# ConverterModule12V18A.net
KiCad netlist of a schematic drawn in Altium Designer
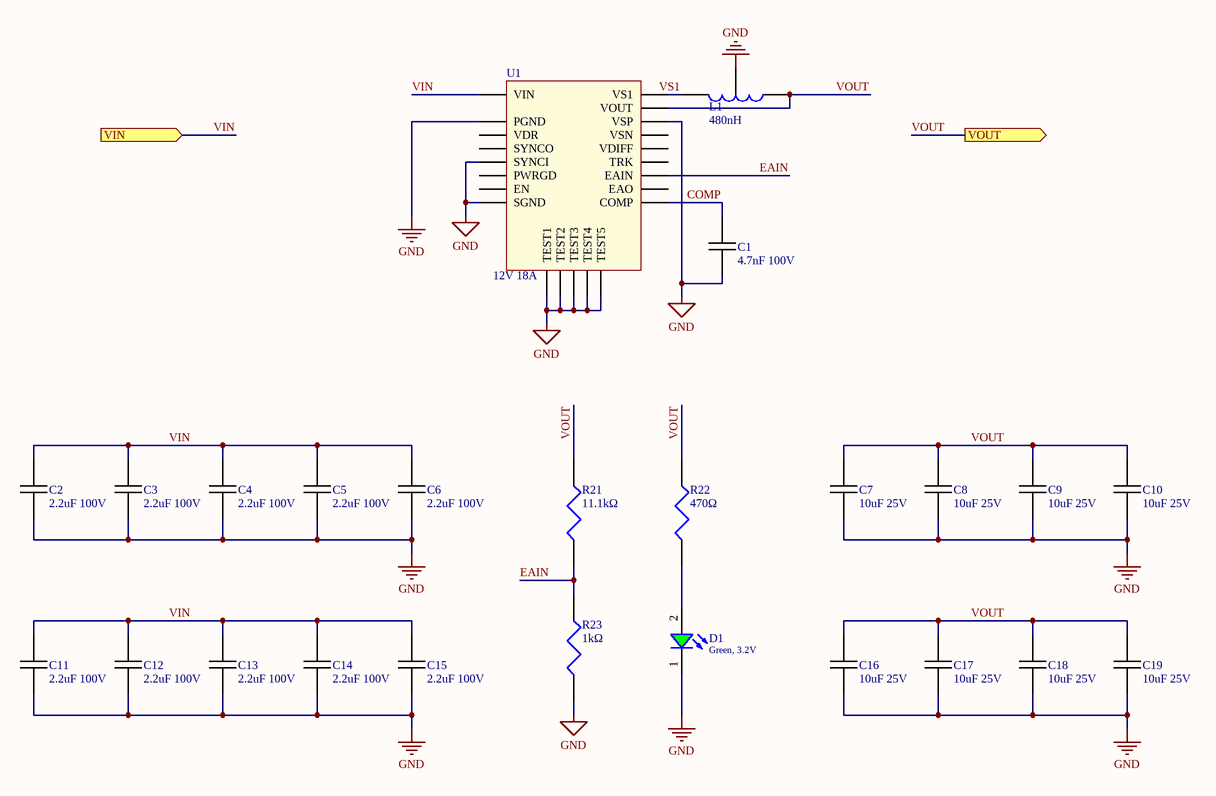
[diagram p0: ConverterModule12V18A.SchDoc]

(export (version "E")
  (design (tool "Eeschema 10.0.6"))
  (components
    (comp (ref "C1")
      (value "4.7nF 100V")
      (footprint "C1608 Generic")
      (description "TDK CAP CER 4700PF 100V C0G 0603")
      (fields
        (field (name "PART NUMBER") "C1608C0G2A472J080AC")
        (field (name "MANUFACTURER") "TDK Corporation")
      )
      (libsource (lib "MinesROV") (part "C1608C0G2A472J080AC"))
    )
    (comp (ref "C2")
      (value "2.2uF 100V")
      (footprint "HMK325B7225MM-P")
      (description "Taiyo Yuden CAP CER 2.2UF 100V X7R 1210")
      (fields (field (name "PART NUMBER") "HMK325B7225MM-P") (field (name "MANUFACTURER") "Taiyo Yuden"))
      (libsource (lib "MinesROV") (part "HMK325B7225MM-P"))
    )
    (comp (ref "C3")
      (value "2.2uF 100V")
      (footprint "HMK325B7225MM-P")
      (description "Taiyo Yuden CAP CER 2.2UF 100V X7R 1210")
      (fields (field (name "PART NUMBER") "HMK325B7225MM-P") (field (name "MANUFACTURER") "Taiyo Yuden"))
      (libsource (lib "MinesROV") (part "HMK325B7225MM-P"))
    )
    (comp (ref "C4")
      (value "2.2uF 100V")
      (footprint "HMK325B7225MM-P")
      (description "Taiyo Yuden CAP CER 2.2UF 100V X7R 1210")
      (fields (field (name "PART NUMBER") "HMK325B7225MM-P") (field (name "MANUFACTURER") "Taiyo Yuden"))
      (libsource (lib "MinesROV") (part "HMK325B7225MM-P"))
    )
    (comp (ref "C5")
      (value "2.2uF 100V")
      (footprint "HMK325B7225MM-P")
      (description "Taiyo Yuden CAP CER 2.2UF 100V X7R 1210")
      (fields (field (name "PART NUMBER") "HMK325B7225MM-P") (field (name "MANUFACTURER") "Taiyo Yuden"))
      (libsource (lib "MinesROV") (part "HMK325B7225MM-P"))
    )
    (comp (ref "C6")
      (value "2.2uF 100V")
      (footprint "HMK325B7225MM-P")
      (description "Taiyo Yuden CAP CER 2.2UF 100V X7R 1210")
      (fields (field (name "PART NUMBER") "HMK325B7225MM-P") (field (name "MANUFACTURER") "Taiyo Yuden"))
      (libsource (lib "MinesROV") (part "HMK325B7225MM-P"))
    )
    (comp (ref "C7")
      (value "10uF 25V")
      (footprint "C1210C106M3RACTU")
      (description "KEMET CAP CER 10UF 25V X7R 1210")
      (fields (field (name "PART NUMBER") "C1210C106M3RACTU") (field (name "MANUFACTURER") "KEMET"))
      (libsource (lib "MinesROV") (part "C1210C106M3RACTU"))
    )
    (comp (ref "C8")
      (value "10uF 25V")
      (footprint "C1210C106M3RACTU")
      (description "KEMET CAP CER 10UF 25V X7R 1210")
      (fields (field (name "PART NUMBER") "C1210C106M3RACTU") (field (name "MANUFACTURER") "KEMET"))
      (libsource (lib "MinesROV") (part "C1210C106M3RACTU"))
    )
    (comp (ref "C9")
      (value "10uF 25V")
      (footprint "C1210C106M3RACTU")
      (description "KEMET CAP CER 10UF 25V X7R 1210")
      (fields (field (name "PART NUMBER") "C1210C106M3RACTU") (field (name "MANUFACTURER") "KEMET"))
      (libsource (lib "MinesROV") (part "C1210C106M3RACTU"))
    )
    (comp (ref "C10")
      (value "10uF 25V")
      (footprint "C1210C106M3RACTU")
      (description "KEMET CAP CER 10UF 25V X7R 1210")
      (fields (field (name "PART NUMBER") "C1210C106M3RACTU") (field (name "MANUFACTURER") "KEMET"))
      (libsource (lib "MinesROV") (part "C1210C106M3RACTU"))
    )
    (comp (ref "C11")
      (value "2.2uF 100V")
      (footprint "HMK325B7225MM-P")
      (description "Taiyo Yuden CAP CER 2.2UF 100V X7R 1210")
      (fields (field (name "PART NUMBER") "HMK325B7225MM-P") (field (name "MANUFACTURER") "Taiyo Yuden"))
      (libsource (lib "MinesROV") (part "HMK325B7225MM-P"))
    )
    (comp (ref "C12")
      (value "2.2uF 100V")
      (footprint "HMK325B7225MM-P")
      (description "Taiyo Yuden CAP CER 2.2UF 100V X7R 1210")
      (fields (field (name "PART NUMBER") "HMK325B7225MM-P") (field (name "MANUFACTURER") "Taiyo Yuden"))
      (libsource (lib "MinesROV") (part "HMK325B7225MM-P"))
    )
    (comp (ref "C13")
      (value "2.2uF 100V")
      (footprint "HMK325B7225MM-P")
      (description "Taiyo Yuden CAP CER 2.2UF 100V X7R 1210")
      (fields (field (name "PART NUMBER") "HMK325B7225MM-P") (field (name "MANUFACTURER") "Taiyo Yuden"))
      (libsource (lib "MinesROV") (part "HMK325B7225MM-P"))
    )
    (comp (ref "C14")
      (value "2.2uF 100V")
      (footprint "HMK325B7225MM-P")
      (description "Taiyo Yuden CAP CER 2.2UF 100V X7R 1210")
      (fields (field (name "PART NUMBER") "HMK325B7225MM-P") (field (name "MANUFACTURER") "Taiyo Yuden"))
      (libsource (lib "MinesROV") (part "HMK325B7225MM-P"))
    )
    (comp (ref "C15")
      (value "2.2uF 100V")
      (footprint "HMK325B7225MM-P")
      (description "Taiyo Yuden CAP CER 2.2UF 100V X7R 1210")
      (fields (field (name "PART NUMBER") "HMK325B7225MM-P") (field (name "MANUFACTURER") "Taiyo Yuden"))
      (libsource (lib "MinesROV") (part "HMK325B7225MM-P"))
    )
    (comp (ref "C16")
      (value "10uF 25V")
      (footprint "C1210C106M3RACTU")
      (description "KEMET CAP CER 10UF 25V X7R 1210")
      (fields (field (name "PART NUMBER") "C1210C106M3RACTU") (field (name "MANUFACTURER") "KEMET"))
      (libsource (lib "MinesROV") (part "C1210C106M3RACTU"))
    )
    (comp (ref "C17")
      (value "10uF 25V")
      (footprint "C1210C106M3RACTU")
      (description "KEMET CAP CER 10UF 25V X7R 1210")
      (fields (field (name "PART NUMBER") "C1210C106M3RACTU") (field (name "MANUFACTURER") "KEMET"))
      (libsource (lib "MinesROV") (part "C1210C106M3RACTU"))
    )
    (comp (ref "C18")
      (value "10uF 25V")
      (footprint "C1210C106M3RACTU")
      (description "KEMET CAP CER 10UF 25V X7R 1210")
      (fields (field (name "PART NUMBER") "C1210C106M3RACTU") (field (name "MANUFACTURER") "KEMET"))
      (libsource (lib "MinesROV") (part "C1210C106M3RACTU"))
    )
    (comp (ref "C19")
      (value "10uF 25V")
      (footprint "C1210C106M3RACTU")
      (description "KEMET CAP CER 10UF 25V X7R 1210")
      (fields (field (name "PART NUMBER") "C1210C106M3RACTU") (field (name "MANUFACTURER") "KEMET"))
      (libsource (lib "MinesROV") (part "C1210C106M3RACTU"))
    )
    (comp (ref "D1")
      (value "Green, 3.2V")
      (footprint "WL-SMCW_1206")
      (description "WL-SMCW SMT Mono-color Chip LED Waterclear, size 1206, Green, 3.2V, 140deg")
      (fields (field (name "PART NUMBER") "150120GS75000") (field (name "PUBLISHER") "Wurth Elektronik"))
      (libsource (lib "MinesROV") (part "150120GS75000"))
    )
    (comp (ref "L1")
      (value "480nH")
      (footprint "PA5120.481NLT")
      (description "Pulse FIXED IND 480NH 32A 1.7MOHM SMD")
      (fields
        (field (name "MANUFACTURER") "Pulse Electronics Power")
        (field (name "PART NUMBER") "PA5120.481NLT")
      )
      (libsource (lib "MinesROV") (part "PA5120.481NLT"))
    )
    (comp (ref "R21")
      (value "11.1kΩ")
      (footprint "RNCF0603 Generic")
      (description "Stackpole RES 11.1K OHM 0.1% 1/10W 0603")
      (fields
        (field (name "PART NUMBER") "RNCF0603BTE11K1")
        (field (name "MANUFACTURER") "Stackpole Electronics Inc")
      )
      (libsource (lib "MinesROV") (part "RNCF0603BTE11K1"))
    )
    (comp (ref "R22")
      (value "470Ω")
      (footprint "RMCF1206")
      (description "Stackpole RES 470 OHM 5% 1/4W 1206")
      (fields
        (field (name "PART NUMBER") "RMCF1206JT470R")
        (field (name "MANUFACTURER") "Stackpole Electronics Inc")
      )
      (libsource (lib "MinesROV") (part "RMCF1206JT470R"))
    )
    (comp (ref "R23")
      (value "1kΩ")
      (footprint "RNCF0603 Generic")
      (description "Stackpole RES 1K OHM 0.01% 1/10W 0603")
      (fields
        (field (name "PART NUMBER") "RNCF0603TKY1K00")
        (field (name "MANUFACTURER") "Stackpole Electronics Inc")
      )
      (libsource (lib "MinesROV") (part "RNCF0603TKY1K00"))
    )
    (comp (ref "U1")
      (value "12V 18A")
      (footprint "PI3526-00-LGIZ")
      (description "Vicor DC DC CONVERTER 12V 18A")
      (fields (field (name "MANUFACTURER") "Vicor Corporation") (field (name "PART NUMBER") "PI3526-00-LGIZ"))
      (libsource (lib "MinesROV") (part "PI3526-00-LGIZ"))
    )
  )
  (nets
    (net (code "1") (name "/COMP") (class "Default")
      (node (ref "C1") (pin "1") (pinfunction "1_1") (pintype "passive"))
      (node (ref "U1") (pin "B1") (pinfunction "COMP_B1") (pintype "passive"))
    )
    (net (code "2") (name "/EAIN") (class "Default")
      (node (ref "R21") (pin "2") (pinfunction "2_2") (pintype "passive"))
      (node (ref "R23") (pin "2") (pinfunction "2_2") (pintype "passive"))
      (node (ref "U1") (pin "A2") (pinfunction "EAIN_A2") (pintype "passive"))
    )
    (net (code "3") (name "/VIN") (class "Default")
      (node (ref "C11") (pin "1") (pinfunction "1_1") (pintype "passive"))
      (node (ref "C12") (pin "1") (pinfunction "1_1") (pintype "passive"))
      (node (ref "C13") (pin "1") (pinfunction "1_1") (pintype "passive"))
      (node (ref "C14") (pin "1") (pinfunction "1_1") (pintype "passive"))
      (node (ref "C15") (pin "1") (pinfunction "1_1") (pintype "passive"))
      (node (ref "C2") (pin "1") (pinfunction "1_1") (pintype "passive"))
      (node (ref "C3") (pin "1") (pinfunction "1_1") (pintype "passive"))
      (node (ref "C4") (pin "1") (pinfunction "1_1") (pintype "passive"))
      (node (ref "C5") (pin "1") (pinfunction "1_1") (pintype "passive"))
      (node (ref "C6") (pin "1") (pinfunction "1_1") (pintype "passive"))
      (node (ref "U1") (pin "BLOCK3") (pinfunction "VIN_BLOCK3") (pintype "passive"))
    )
    (net (code "4") (name "/VOUT") (class "Default")
      (node (ref "C10") (pin "2") (pinfunction "2_2") (pintype "passive"))
      (node (ref "C16") (pin "2") (pinfunction "2_2") (pintype "passive"))
      (node (ref "C17") (pin "2") (pinfunction "2_2") (pintype "passive"))
      (node (ref "C18") (pin "2") (pinfunction "2_2") (pintype "passive"))
      (node (ref "C19") (pin "2") (pinfunction "2_2") (pintype "passive"))
      (node (ref "C7") (pin "2") (pinfunction "2_2") (pintype "passive"))
      (node (ref "C8") (pin "2") (pinfunction "2_2") (pintype "passive"))
      (node (ref "C9") (pin "2") (pinfunction "2_2") (pintype "passive"))
      (node (ref "L1") (pin "1") (pinfunction "1_1") (pintype "passive"))
      (node (ref "R21") (pin "1") (pinfunction "1_1") (pintype "passive"))
      (node (ref "R22") (pin "2") (pinfunction "2_2") (pintype "passive"))
      (node (ref "U1") (pin "BLOCK4") (pinfunction "VOUT_BLOCK4") (pintype "passive"))
    )
    (net (code "5") (name "/VS1") (class "Default")
      (node (ref "L1") (pin "2") (pinfunction "2_2") (pintype "passive"))
      (node (ref "U1") (pin "BLOCK1") (pinfunction "VS1_BLOCK1") (pintype "passive"))
    )
    (net (code "6") (name "GND") (class "Default")
      (node (ref "C1") (pin "2") (pinfunction "2_2") (pintype "passive"))
      (node (ref "C10") (pin "1") (pinfunction "1_1") (pintype "passive"))
      (node (ref "C11") (pin "2") (pinfunction "2_2") (pintype "passive"))
      (node (ref "C12") (pin "2") (pinfunction "2_2") (pintype "passive"))
      (node (ref "C13") (pin "2") (pinfunction "2_2") (pintype "passive"))
      (node (ref "C14") (pin "2") (pinfunction "2_2") (pintype "passive"))
      (node (ref "C15") (pin "2") (pinfunction "2_2") (pintype "passive"))
      (node (ref "C16") (pin "1") (pinfunction "1_1") (pintype "passive"))
      (node (ref "C17") (pin "1") (pinfunction "1_1") (pintype "passive"))
      (node (ref "C18") (pin "1") (pinfunction "1_1") (pintype "passive"))
      (node (ref "C19") (pin "1") (pinfunction "1_1") (pintype "passive"))
      (node (ref "C2") (pin "2") (pinfunction "2_2") (pintype "passive"))
      (node (ref "C3") (pin "2") (pinfunction "2_2") (pintype "passive"))
      (node (ref "C4") (pin "2") (pinfunction "2_2") (pintype "passive"))
      (node (ref "C5") (pin "2") (pinfunction "2_2") (pintype "passive"))
      (node (ref "C6") (pin "2") (pinfunction "2_2") (pintype "passive"))
      (node (ref "C7") (pin "1") (pinfunction "1_1") (pintype "passive"))
      (node (ref "C8") (pin "1") (pinfunction "1_1") (pintype "passive"))
      (node (ref "C9") (pin "1") (pinfunction "1_1") (pintype "passive"))
      (node (ref "D1") (pin "1") (pinfunction "K_1") (pintype "passive"))
      (node (ref "L1") (pin "3") (pinfunction "3_3") (pintype "passive"))
      (node (ref "R23") (pin "1") (pinfunction "1_1") (pintype "passive"))
      (node (ref "U1") (pin "A5") (pinfunction "VSP_A5") (pintype "passive"))
      (node (ref "U1") (pin "BLOCK2") (pinfunction "PGND_BLOCK2") (pintype "passive"))
      (node (ref "U1") (pin "BLOCK5") (pinfunction "SGND_BLOCK5") (pintype "passive"))
      (node (ref "U1") (pin "E1") (pinfunction "TEST5_E1") (pintype "passive"))
      (node (ref "U1") (pin "H1") (pinfunction "TEST4_H1") (pintype "passive"))
      (node (ref "U1") (pin "J1") (pinfunction "TEST3_J1") (pintype "passive"))
      (node (ref "U1") (pin "K1") (pinfunction "TEST2_K1") (pintype "passive"))
      (node (ref "U1") (pin "K2") (pinfunction "TEST1_K2") (pintype "passive"))
      (node (ref "U1") (pin "K4") (pinfunction "SYNCI_K4") (pintype "passive"))
    )
    (net (code "7") (name "Net-(D1-A)") (class "Default")
      (node (ref "D1") (pin "2") (pinfunction "A_2") (pintype "passive"))
      (node (ref "R22") (pin "1") (pinfunction "1_1") (pintype "passive"))
    )
    (net (code "8") (name "unconnected-(U1-EAO-PadA1)") (class "Default")
      (node (ref "U1") (pin "A1") (pinfunction "EAO_A1") (pintype "passive"))
    )
    (net (code "9") (name "unconnected-(U1-EN-PadF1)") (class "Default")
      (node (ref "U1") (pin "F1") (pinfunction "EN_F1") (pintype "passive"))
    )
    (net (code "10") (name "unconnected-(U1-PWRGD-PadG1)") (class "Default")
      (node (ref "U1") (pin "G1") (pinfunction "PWRGD_G1") (pintype "passive"))
    )
    (net (code "11") (name "unconnected-(U1-SYNCO-PadK3)") (class "Default")
      (node (ref "U1") (pin "K3") (pinfunction "SYNCO_K3") (pintype "passive"))
    )
    (net (code "12") (name "unconnected-(U1-TRK-PadC1)") (class "Default")
      (node (ref "U1") (pin "C1") (pinfunction "TRK_C1") (pintype "passive"))
    )
    (net (code "13") (name "unconnected-(U1-VDIFF-PadA3)") (class "Default")
      (node (ref "U1") (pin "A3") (pinfunction "VDIFF_A3") (pintype "passive"))
    )
    (net (code "14") (name "unconnected-(U1-VDR-PadK5)") (class "Default")
      (node (ref "U1") (pin "K5") (pinfunction "VDR_K5") (pintype "passive"))
    )
    (net (code "15") (name "unconnected-(U1-VSN-PadA4)") (class "Default")
      (node (ref "U1") (pin "A4") (pinfunction "VSN_A4") (pintype "passive"))
    )
  )
)
